# M2_USB_SATA.net
KiCad netlist of a schematic drawn in Altium Designer
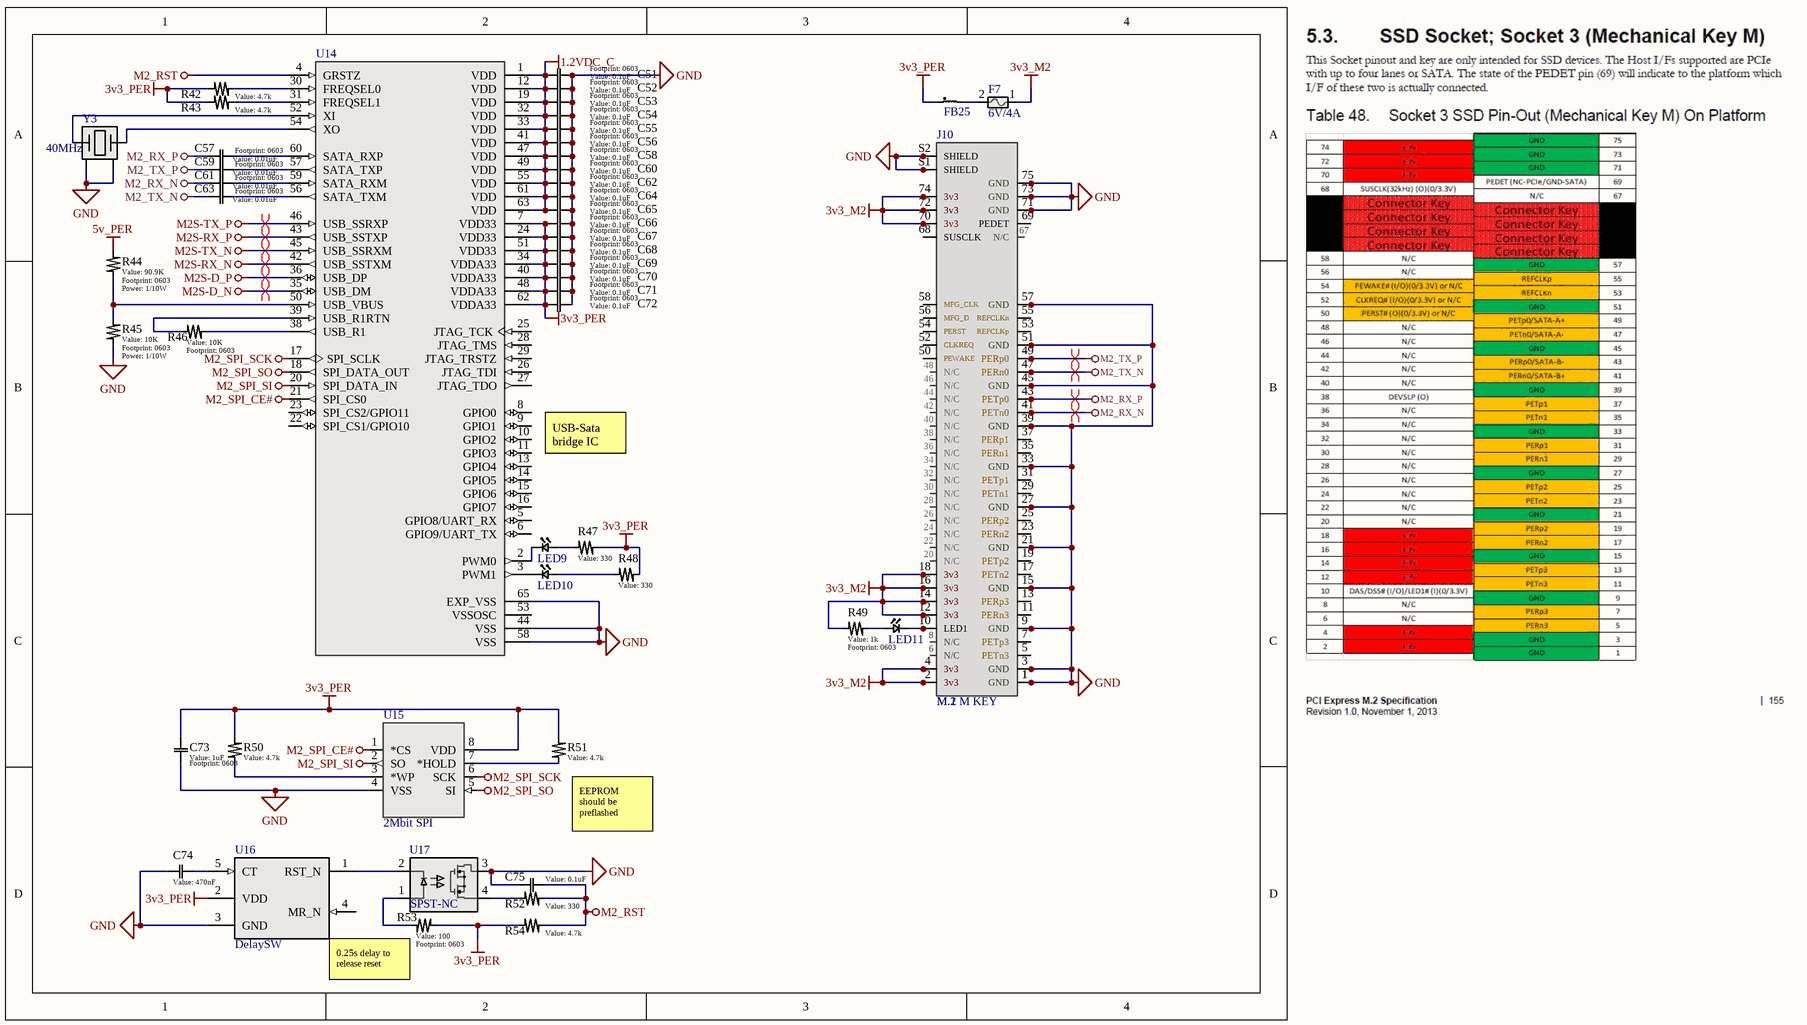
[diagram p0: M2_USB_SATA.SchDoc]

(export (version "E")
  (design (tool "Eeschema 10.0.6"))
  (components
    (comp (ref "C51")
      (value "0.1uF")
      (footprint "0603")
      (fields
        (field (name "VOLTAGE") "10V")
        (field (name "TOLERANCE") "10%")
        (field (name "Comment") "Generic Capacitor")
      )
      (libsource (lib "Capacitors") (part "Generic Capacitor"))
    )
    (comp (ref "C52")
      (value "0.1uF")
      (footprint "0603")
      (fields
        (field (name "VOLTAGE") "10V")
        (field (name "TOLERANCE") "10%")
        (field (name "Comment") "Generic Capacitor")
      )
      (libsource (lib "Capacitors") (part "Generic Capacitor"))
    )
    (comp (ref "C53")
      (value "0.1uF")
      (footprint "0603")
      (fields
        (field (name "VOLTAGE") "10V")
        (field (name "TOLERANCE") "10%")
        (field (name "Comment") "Generic Capacitor")
      )
      (libsource (lib "Capacitors") (part "Generic Capacitor"))
    )
    (comp (ref "C54")
      (value "0.1uF")
      (footprint "0603")
      (fields
        (field (name "VOLTAGE") "10V")
        (field (name "TOLERANCE") "10%")
        (field (name "Comment") "Generic Capacitor")
      )
      (libsource (lib "Capacitors") (part "Generic Capacitor"))
    )
    (comp (ref "C55")
      (value "0.1uF")
      (footprint "0603")
      (fields
        (field (name "VOLTAGE") "10V")
        (field (name "TOLERANCE") "10%")
        (field (name "Comment") "Generic Capacitor")
      )
      (libsource (lib "Capacitors") (part "Generic Capacitor"))
    )
    (comp (ref "C56")
      (value "0.1uF")
      (footprint "0603")
      (fields
        (field (name "VOLTAGE") "10V")
        (field (name "TOLERANCE") "10%")
        (field (name "Comment") "Generic Capacitor")
      )
      (libsource (lib "Capacitors") (part "Generic Capacitor"))
    )
    (comp (ref "C57")
      (value "0.01uF")
      (footprint "0603")
      (fields
        (field (name "VOLTAGE") "10V")
        (field (name "TOLERANCE") "10%")
        (field (name "Comment") "Generic Capacitor")
      )
      (libsource (lib "Capacitors") (part "Generic Capacitor"))
    )
    (comp (ref "C58")
      (value "0.1uF")
      (footprint "0603")
      (fields
        (field (name "VOLTAGE") "10V")
        (field (name "TOLERANCE") "10%")
        (field (name "Comment") "Generic Capacitor")
      )
      (libsource (lib "Capacitors") (part "Generic Capacitor"))
    )
    (comp (ref "C59")
      (value "0.01uF")
      (footprint "0603")
      (fields
        (field (name "VOLTAGE") "10V")
        (field (name "TOLERANCE") "10%")
        (field (name "Comment") "Generic Capacitor")
      )
      (libsource (lib "Capacitors") (part "Generic Capacitor"))
    )
    (comp (ref "C60")
      (value "0.1uF")
      (footprint "0603")
      (fields
        (field (name "VOLTAGE") "10V")
        (field (name "TOLERANCE") "10%")
        (field (name "Comment") "Generic Capacitor")
      )
      (libsource (lib "Capacitors") (part "Generic Capacitor"))
    )
    (comp (ref "C61")
      (value "0.01uF")
      (footprint "0603")
      (fields
        (field (name "VOLTAGE") "10V")
        (field (name "TOLERANCE") "10%")
        (field (name "Comment") "Generic Capacitor")
      )
      (libsource (lib "Capacitors") (part "Generic Capacitor"))
    )
    (comp (ref "C62")
      (value "0.1uF")
      (footprint "0603")
      (fields
        (field (name "VOLTAGE") "10V")
        (field (name "TOLERANCE") "10%")
        (field (name "Comment") "Generic Capacitor")
      )
      (libsource (lib "Capacitors") (part "Generic Capacitor"))
    )
    (comp (ref "C63")
      (value "0.01uF")
      (footprint "0603")
      (fields
        (field (name "VOLTAGE") "10V")
        (field (name "TOLERANCE") "10%")
        (field (name "Comment") "Generic Capacitor")
      )
      (libsource (lib "Capacitors") (part "Generic Capacitor"))
    )
    (comp (ref "C64")
      (value "0.1uF")
      (footprint "0603")
      (fields
        (field (name "VOLTAGE") "10V")
        (field (name "TOLERANCE") "10%")
        (field (name "Comment") "Generic Capacitor")
      )
      (libsource (lib "Capacitors") (part "Generic Capacitor"))
    )
    (comp (ref "C65")
      (value "0.1uF")
      (footprint "0603")
      (fields
        (field (name "VOLTAGE") "10V")
        (field (name "TOLERANCE") "10%")
        (field (name "Comment") "Generic Capacitor")
      )
      (libsource (lib "Capacitors") (part "Generic Capacitor"))
    )
    (comp (ref "C66")
      (value "0.1uF")
      (footprint "0603")
      (fields
        (field (name "VOLTAGE") "10V")
        (field (name "TOLERANCE") "10%")
        (field (name "Comment") "Generic Capacitor")
      )
      (libsource (lib "Capacitors") (part "Generic Capacitor"))
    )
    (comp (ref "C67")
      (value "0.1uF")
      (footprint "0603")
      (fields
        (field (name "VOLTAGE") "10V")
        (field (name "TOLERANCE") "10%")
        (field (name "Comment") "Generic Capacitor")
      )
      (libsource (lib "Capacitors") (part "Generic Capacitor"))
    )
    (comp (ref "C68")
      (value "0.1uF")
      (footprint "0603")
      (fields
        (field (name "VOLTAGE") "10V")
        (field (name "TOLERANCE") "10%")
        (field (name "Comment") "Generic Capacitor")
      )
      (libsource (lib "Capacitors") (part "Generic Capacitor"))
    )
    (comp (ref "C69")
      (value "0.1uF")
      (footprint "0603")
      (fields
        (field (name "VOLTAGE") "10V")
        (field (name "TOLERANCE") "10%")
        (field (name "Comment") "Generic Capacitor")
      )
      (libsource (lib "Capacitors") (part "Generic Capacitor"))
    )
    (comp (ref "C70")
      (value "0.1uF")
      (footprint "0603")
      (fields
        (field (name "VOLTAGE") "10V")
        (field (name "TOLERANCE") "10%")
        (field (name "Comment") "Generic Capacitor")
      )
      (libsource (lib "Capacitors") (part "Generic Capacitor"))
    )
    (comp (ref "C71")
      (value "0.1uF")
      (footprint "0603")
      (fields
        (field (name "VOLTAGE") "10V")
        (field (name "TOLERANCE") "10%")
        (field (name "Comment") "Generic Capacitor")
      )
      (libsource (lib "Capacitors") (part "Generic Capacitor"))
    )
    (comp (ref "C72")
      (value "0.1uF")
      (footprint "0603")
      (fields
        (field (name "VOLTAGE") "10V")
        (field (name "TOLERANCE") "10%")
        (field (name "Comment") "Generic Capacitor")
      )
      (libsource (lib "Capacitors") (part "Generic Capacitor"))
    )
    (comp (ref "C73")
      (value "1uF")
      (footprint "0603")
      (fields
        (field (name "VOLTAGE") ">10V")
        (field (name "TOLERANCE") "10%")
        (field (name "Comment") "Generic Capacitor")
      )
      (libsource (lib "Capacitors") (part "Generic Capacitor"))
    )
    (comp (ref "C74")
      (value "470nF")
      (footprint "0603")
      (fields
        (field (name "VOLTAGE") "10V")
        (field (name "TOLERANCE") "10%")
        (field (name "Comment") "Generic Capacitor")
      )
      (libsource (lib "Capacitors") (part "Generic Capacitor"))
    )
    (comp (ref "C75")
      (value "0.1uF")
      (footprint "0603")
      (fields
        (field (name "VOLTAGE") "10V")
        (field (name "TOLERANCE") "10%")
        (field (name "Comment") "Generic Capacitor")
      )
      (libsource (lib "Capacitors") (part "Generic Capacitor"))
    )
    (comp (ref "F7")
      (value "6V/4A")
      (footprint "0805")
      (description "Polymeric PTC Resettable Fuse 6V 1 A Ih Surface Mount 0805 (2012 Metric), Concave")
      (fields (field (name "MANUFACTURER") "Bel") (field (name "MANUFACTURER PART NUMBER") "0ZCK0100FF2E"))
      (libsource (lib "Regulators") (part "0ZCK0100FF2E"))
    )
    (comp (ref "FB25")
      (value "1206 Ferrite")
      (footprint "1206")
      (description "160 Ohms @ 100MHz 1 Power, Signal Line Ferrite Bead 1206 (3216 Metric) 6A 18mOhm")
      (libsource (lib "Inductors") (part "HI1206T161R-10"))
    )
    (comp (ref "J10")
      (value "M.2 M KEY")
      (footprint "1-2199230-6")
      (description "M.2 0.5PITCH 4.2H KEY M 30U AU")
      (fields (field (name "MF") "TE Connectivity") (field (name "DIGI-KEY_PART_NUMBER") "A118046TR-ND"))
      (libsource (lib "Connectors") (part "1-2199230-6"))
    )
    (comp (ref "LED9")
      (value "LTST-C191KGKT")
      (footprint "0603 (1608 Metric) Concave")
      (description "LED Uni-Color Green 574nm 2-Pin Chip LED T/R")
      (libsource (lib "Gamber - Johnson LLC") (part "LTST-C191KGKT"))
    )
    (comp (ref "LED10")
      (value "LTST-C191KGKT")
      (footprint "0603 (1608 Metric) Concave")
      (description "LED Uni-Color Green 574nm 2-Pin Chip LED T/R")
      (libsource (lib "Gamber - Johnson LLC") (part "LTST-C191KGKT"))
    )
    (comp (ref "LED11")
      (value "LTST-C191KGKT")
      (footprint "0603 (1608 Metric) Concave")
      (description "LED Uni-Color Green 574nm 2-Pin Chip LED T/R")
      (libsource (lib "Gamber - Johnson LLC") (part "LTST-C191KGKT"))
    )
    (comp (ref "M.1")
      (value "NVME Ref")
      (footprint "NVME-Ref 2242")
      (description "Overlay pads w/ 1-2199230-6\r\nUse standoff for mounting screws")
      (libsource (lib "SOC_Carrier") (part "NVME Ref"))
    )
    (comp (ref "R42")
      (value "4.7k")
      (footprint "0603")
      (fields
        (field (name "TOLERANCE") "1%")
        (field (name "POWER") "1/10W")
        (field (name "Comment") "Generic Resistor")
      )
      (libsource (lib "Resistors") (part "Generic Resistor"))
    )
    (comp (ref "R43")
      (value "4.7k")
      (footprint "0603")
      (fields
        (field (name "TOLERANCE") "1%")
        (field (name "POWER") "1/10W")
        (field (name "Comment") "Generic Resistor")
      )
      (libsource (lib "Resistors") (part "Generic Resistor"))
    )
    (comp (ref "R44")
      (value "90.9K")
      (footprint "0603")
      (fields
        (field (name "TOLERANCE") "1%")
        (field (name "POWER") "1/10W")
        (field (name "Comment") "Generic Resistor")
      )
      (libsource (lib "Resistors") (part "Generic Resistor"))
    )
    (comp (ref "R45")
      (value "10K")
      (footprint "0603")
      (fields
        (field (name "TOLERANCE") "1%")
        (field (name "POWER") "1/10W")
        (field (name "Comment") "Generic Resistor")
      )
      (libsource (lib "Resistors") (part "Generic Resistor"))
    )
    (comp (ref "R46")
      (value "10K")
      (footprint "0603")
      (fields
        (field (name "TOLERANCE") "1%")
        (field (name "POWER") "1/10W")
        (field (name "Comment") "Generic Resistor")
      )
      (libsource (lib "Resistors") (part "Generic Resistor"))
    )
    (comp (ref "R47")
      (value "330")
      (footprint "0603")
      (fields
        (field (name "TOLERANCE") "1%")
        (field (name "POWER") "1/10W")
        (field (name "Comment") "Generic Resistor")
      )
      (libsource (lib "Resistors") (part "Generic Resistor"))
    )
    (comp (ref "R48")
      (value "330")
      (footprint "0603")
      (fields
        (field (name "TOLERANCE") "1%")
        (field (name "POWER") "1/10W")
        (field (name "Comment") "Generic Resistor")
      )
      (libsource (lib "Resistors") (part "Generic Resistor"))
    )
    (comp (ref "R49")
      (value "1k")
      (footprint "0603")
      (fields
        (field (name "TOLERANCE") "1%")
        (field (name "POWER") "1/10W")
        (field (name "Comment") "Generic Resistor")
      )
      (libsource (lib "Resistors") (part "Generic Resistor"))
    )
    (comp (ref "R50")
      (value "4.7k")
      (footprint "0603")
      (fields
        (field (name "TOLERANCE") "1%")
        (field (name "POWER") "1/10W")
        (field (name "Comment") "Generic Resistor")
      )
      (libsource (lib "Resistors") (part "Generic Resistor"))
    )
    (comp (ref "R51")
      (value "4.7k")
      (footprint "0603")
      (fields
        (field (name "TOLERANCE") "1%")
        (field (name "POWER") "1/10W")
        (field (name "Comment") "Generic Resistor")
      )
      (libsource (lib "Resistors") (part "Generic Resistor"))
    )
    (comp (ref "R52")
      (value "330")
      (footprint "0603")
      (fields
        (field (name "TOLERANCE") "1%")
        (field (name "POWER") "1/10W")
        (field (name "Comment") "Generic Resistor")
      )
      (libsource (lib "Resistors") (part "Generic Resistor"))
    )
    (comp (ref "R53")
      (value "100")
      (footprint "0603")
      (fields
        (field (name "TOLERANCE") "1%")
        (field (name "POWER") "1/10W")
        (field (name "Comment") "Generic Resistor")
      )
      (libsource (lib "Resistors") (part "Generic Resistor"))
    )
    (comp (ref "R54")
      (value "4.7k")
      (footprint "0603")
      (fields
        (field (name "TOLERANCE") "1%")
        (field (name "POWER") "1/10W")
        (field (name "Comment") "Generic Resistor")
      )
      (libsource (lib "Resistors") (part "Generic Resistor"))
    )
    (comp (ref "U14")
      (value "USB-SATA Bridge")
      (footprint "64-HTQFP (7x7)")
      (description "HDD, CD, DVD Drive Interface 64-HTQFP _7x7_")
      (fields (field (name "MF") "Texas Instruments") (field (name "DIGI-KEY_PART_NUMBER") "296-28827-ND"))
      (libsource (lib "Misc ICs") (part "TUSB9261PVP"))
    )
    (comp (ref "U15")
      (value "2Mbit SPI")
      (footprint "8-SOIC (0.154\", 3.90mm Width)")
      (description "IC FLASH 2MBIT SPI 30MHZ 8SOP")
      (libsource (lib "Misc ICs") (part "LE25U20AMB-AH"))
    )
    (comp (ref "U16")
      (value "DelaySW")
      (footprint "TSOT-23-5")
      (description "Supervisor Open Drain or Open Collector 1 Channel SOT-23-5\r\n2.2V Threshold")
      (libsource (lib "Switches") (part "TPS3840DL22DBVR"))
    )
    (comp (ref "U17")
      (value "SPST-NC")
      (footprint "4-SOP")
      (description "SSR RELAY SPST-NC 400MA 0-60V")
      (libsource (lib "Switches") (part "CPC1117N"))
    )
    (comp (ref "Y3")
      (value "40MHz")
      (footprint "SMD3225-4P")
      (description "40MHz Surface Mount Crystal 10pF ±10ppm SMD3225-4P Crystal")
      (libsource (lib "Clock ICs") (part "L327S400H11L"))
    )
  )
  (nets
    (net (code "1") (name "1.2VDC_C") (class "Default")
      (node (ref "C51") (pin "2") (pinfunction "2_2") (pintype "passive"))
      (node (ref "C52") (pin "2") (pinfunction "2_2") (pintype "passive"))
      (node (ref "C53") (pin "2") (pinfunction "2_2") (pintype "passive"))
      (node (ref "C54") (pin "2") (pinfunction "2_2") (pintype "passive"))
      (node (ref "C55") (pin "2") (pinfunction "2_2") (pintype "passive"))
      (node (ref "C56") (pin "2") (pinfunction "2_2") (pintype "passive"))
      (node (ref "C58") (pin "2") (pinfunction "2_2") (pintype "passive"))
      (node (ref "C60") (pin "2") (pinfunction "2_2") (pintype "passive"))
      (node (ref "C62") (pin "2") (pinfunction "2_2") (pintype "passive"))
      (node (ref "C64") (pin "2") (pinfunction "2_2") (pintype "passive"))
      (node (ref "C65") (pin "2") (pinfunction "2_2") (pintype "passive"))
      (node (ref "U14") (pin "1") (pinfunction "VDD_1") (pintype "power_in"))
      (node (ref "U14") (pin "12") (pinfunction "VDD_12") (pintype "power_in"))
      (node (ref "U14") (pin "19") (pinfunction "VDD_19") (pintype "power_in"))
      (node (ref "U14") (pin "32") (pinfunction "VDD_32") (pintype "power_in"))
      (node (ref "U14") (pin "33") (pinfunction "VDD_33") (pintype "power_in"))
      (node (ref "U14") (pin "41") (pinfunction "VDD_41") (pintype "power_in"))
      (node (ref "U14") (pin "47") (pinfunction "VDD_47") (pintype "power_in"))
      (node (ref "U14") (pin "49") (pinfunction "VDD_49") (pintype "power_in"))
      (node (ref "U14") (pin "55") (pinfunction "VDD_55") (pintype "power_in"))
      (node (ref "U14") (pin "61") (pinfunction "VDD_61") (pintype "power_in"))
      (node (ref "U14") (pin "63") (pinfunction "VDD_63") (pintype "power_in"))
    )
    (net (code "2") (name "3v3_M2") (class "Default")
      (node (ref "F7") (pin "1") (pinfunction "1_1") (pintype "passive"))
      (node (ref "J10") (pin "12") (pinfunction "3v3_12") (pintype "passive"))
      (node (ref "J10") (pin "14") (pinfunction "3v3_14") (pintype "passive"))
      (node (ref "J10") (pin "16") (pinfunction "3v3_16") (pintype "passive"))
      (node (ref "J10") (pin "18") (pinfunction "3v3_18") (pintype "passive"))
      (node (ref "J10") (pin "2") (pinfunction "3v3_2") (pintype "passive"))
      (node (ref "J10") (pin "4") (pinfunction "3v3_4") (pintype "passive"))
      (node (ref "J10") (pin "70") (pinfunction "3v3_70") (pintype "passive"))
      (node (ref "J10") (pin "72") (pinfunction "3v3_72") (pintype "passive"))
      (node (ref "J10") (pin "74") (pinfunction "3v3_74") (pintype "passive"))
      (node (ref "M.1") (pin "12") (pinfunction "3v3_12") (pintype "passive"))
      (node (ref "M.1") (pin "14") (pinfunction "3v3_14") (pintype "passive"))
      (node (ref "M.1") (pin "16") (pinfunction "3v3_16") (pintype "passive"))
      (node (ref "M.1") (pin "18") (pinfunction "3v3_18") (pintype "passive"))
      (node (ref "M.1") (pin "2") (pinfunction "3v3_2") (pintype "passive"))
      (node (ref "M.1") (pin "4") (pinfunction "3v3_4") (pintype "passive"))
      (node (ref "M.1") (pin "70") (pinfunction "3v3_70") (pintype "passive"))
      (node (ref "M.1") (pin "72") (pinfunction "3v3_72") (pintype "passive"))
      (node (ref "M.1") (pin "74") (pinfunction "3v3_74") (pintype "passive"))
      (node (ref "R49") (pin "2") (pinfunction "2_2") (pintype "passive"))
    )
    (net (code "3") (name "3v3_PER") (class "Default")
      (node (ref "C66") (pin "2") (pinfunction "2_2") (pintype "passive"))
      (node (ref "C67") (pin "2") (pinfunction "2_2") (pintype "passive"))
      (node (ref "C68") (pin "2") (pinfunction "2_2") (pintype "passive"))
      (node (ref "C69") (pin "2") (pinfunction "2_2") (pintype "passive"))
      (node (ref "C70") (pin "2") (pinfunction "2_2") (pintype "passive"))
      (node (ref "C71") (pin "2") (pinfunction "2_2") (pintype "passive"))
      (node (ref "C72") (pin "2") (pinfunction "2_2") (pintype "passive"))
      (node (ref "C73") (pin "1") (pinfunction "1_1") (pintype "passive"))
      (node (ref "FB25") (pin "1") (pinfunction "1_1") (pintype "passive"))
      (node (ref "R42") (pin "1") (pinfunction "1_1") (pintype "passive"))
      (node (ref "R43") (pin "1") (pinfunction "1_1") (pintype "passive"))
      (node (ref "R47") (pin "2") (pinfunction "2_2") (pintype "passive"))
      (node (ref "R48") (pin "2") (pinfunction "2_2") (pintype "passive"))
      (node (ref "R50") (pin "1") (pinfunction "1_1") (pintype "passive"))
      (node (ref "R51") (pin "1") (pinfunction "1_1") (pintype "passive"))
      (node (ref "R53") (pin "2") (pinfunction "2_2") (pintype "passive"))
      (node (ref "R54") (pin "1") (pinfunction "1_1") (pintype "passive"))
      (node (ref "U14") (pin "24") (pinfunction "VDD33_24") (pintype "power_in"))
      (node (ref "U14") (pin "34") (pinfunction "VDDA33_34") (pintype "power_in"))
      (node (ref "U14") (pin "40") (pinfunction "VDDA33_40") (pintype "power_in"))
      (node (ref "U14") (pin "48") (pinfunction "VDDA33_48") (pintype "power_in"))
      (node (ref "U14") (pin "51") (pinfunction "VDD33_51") (pintype "power_in"))
      (node (ref "U14") (pin "62") (pinfunction "VDDA33_62") (pintype "power_in"))
      (node (ref "U14") (pin "7") (pinfunction "VDD33_7") (pintype "power_in"))
      (node (ref "U15") (pin "8") (pinfunction "VDD_8") (pintype "power_in"))
      (node (ref "U16") (pin "2") (pinfunction "VDD_2") (pintype "power_in"))
    )
    (net (code "4") (name "5v_PER") (class "Default")
      (node (ref "R44") (pin "1") (pinfunction "1_1") (pintype "passive"))
    )
    (net (code "5") (name "GND") (class "Default")
      (node (ref "C51") (pin "1") (pinfunction "1_1") (pintype "passive"))
      (node (ref "C52") (pin "1") (pinfunction "1_1") (pintype "passive"))
      (node (ref "C53") (pin "1") (pinfunction "1_1") (pintype "passive"))
      (node (ref "C54") (pin "1") (pinfunction "1_1") (pintype "passive"))
      (node (ref "C55") (pin "1") (pinfunction "1_1") (pintype "passive"))
      (node (ref "C56") (pin "1") (pinfunction "1_1") (pintype "passive"))
      (node (ref "C58") (pin "1") (pinfunction "1_1") (pintype "passive"))
      (node (ref "C60") (pin "1") (pinfunction "1_1") (pintype "passive"))
      (node (ref "C62") (pin "1") (pinfunction "1_1") (pintype "passive"))
      (node (ref "C64") (pin "1") (pinfunction "1_1") (pintype "passive"))
      (node (ref "C65") (pin "1") (pinfunction "1_1") (pintype "passive"))
      (node (ref "C66") (pin "1") (pinfunction "1_1") (pintype "passive"))
      (node (ref "C67") (pin "1") (pinfunction "1_1") (pintype "passive"))
      (node (ref "C68") (pin "1") (pinfunction "1_1") (pintype "passive"))
      (node (ref "C69") (pin "1") (pinfunction "1_1") (pintype "passive"))
      (node (ref "C70") (pin "1") (pinfunction "1_1") (pintype "passive"))
      (node (ref "C71") (pin "1") (pinfunction "1_1") (pintype "passive"))
      (node (ref "C72") (pin "1") (pinfunction "1_1") (pintype "passive"))
      (node (ref "C73") (pin "2") (pinfunction "2_2") (pintype "passive"))
      (node (ref "C74") (pin "2") (pinfunction "2_2") (pintype "passive"))
      (node (ref "C75") (pin "1") (pinfunction "1_1") (pintype "passive"))
      (node (ref "J10") (pin "1") (pinfunction "GND_1") (pintype "passive"))
      (node (ref "J10") (pin "15") (pinfunction "GND_15") (pintype "passive"))
      (node (ref "J10") (pin "21") (pinfunction "GND_21") (pintype "passive"))
      (node (ref "J10") (pin "27") (pinfunction "GND_27") (pintype "passive"))
      (node (ref "J10") (pin "3") (pinfunction "GND_3") (pintype "passive"))
      (node (ref "J10") (pin "33") (pinfunction "GND_33") (pintype "passive"))
      (node (ref "J10") (pin "39") (pinfunction "GND_39") (pintype "passive"))
      (node (ref "J10") (pin "45") (pinfunction "GND_45") (pintype "passive"))
      (node (ref "J10") (pin "51") (pinfunction "GND_51") (pintype "passive"))
      (node (ref "J10") (pin "57") (pinfunction "GND_57") (pintype "passive"))
      (node (ref "J10") (pin "71") (pinfunction "GND_71") (pintype "passive"))
      (node (ref "J10") (pin "73") (pinfunction "GND_73") (pintype "passive"))
      (node (ref "J10") (pin "75") (pinfunction "GND_75") (pintype "passive"))
      (node (ref "J10") (pin "9") (pinfunction "GND_9") (pintype "passive"))
      (node (ref "J10") (pin "S1") (pinfunction "SHIELD_S1") (pintype "passive"))
      (node (ref "J10") (pin "S2") (pinfunction "SHIELD_S2") (pintype "passive"))
      (node (ref "M.1") (pin "1") (pinfunction "GND_1") (pintype "passive"))
      (node (ref "M.1") (pin "15") (pinfunction "GND_15") (pintype "passive"))
      (node (ref "M.1") (pin "21") (pinfunction "GND_21") (pintype "passive"))
      (node (ref "M.1") (pin "27") (pinfunction "GND_27") (pintype "passive"))
      (node (ref "M.1") (pin "3") (pinfunction "GND_3") (pintype "passive"))
      (node (ref "M.1") (pin "33") (pinfunction "GND_33") (pintype "passive"))
      (node (ref "M.1") (pin "39") (pinfunction "GND_39") (pintype "passive"))
      (node (ref "M.1") (pin "45") (pinfunction "GND_45") (pintype "passive"))
      (node (ref "M.1") (pin "51") (pinfunction "GND_51") (pintype "passive"))
      (node (ref "M.1") (pin "57") (pinfunction "GND_57") (pintype "passive"))
      (node (ref "M.1") (pin "71") (pinfunction "GND_71") (pintype "passive"))
      (node (ref "M.1") (pin "73") (pinfunction "GND_73") (pintype "passive"))
      (node (ref "M.1") (pin "75") (pinfunction "GND_75") (pintype "passive"))
      (node (ref "M.1") (pin "9") (pinfunction "GND_9") (pintype "passive"))
      (node (ref "M.1") (pin "S1") (pinfunction "SHIELD_S1") (pintype "passive"))
      (node (ref "M.1") (pin "S2") (pinfunction "SHIELD_S2") (pintype "passive"))
      (node (ref "M.1") (pin "SHD") (pinfunction "SHIELD_SHD") (pintype "passive"))
      (node (ref "R45") (pin "1") (pinfunction "1_1") (pintype "passive"))
      (node (ref "U14") (pin "44") (pinfunction "VSS_44") (pintype "power_in"))
      (node (ref "U14") (pin "58") (pinfunction "VSS_58") (pintype "power_in"))
      (node (ref "U14") (pin "65") (pinfunction "EXP_VSS_65") (pintype "power_in"))
      (node (ref "U15") (pin "4") (pinfunction "VSS_4") (pintype "power_in"))
      (node (ref "U16") (pin "3") (pinfunction "GND_3") (pintype "power_in"))
      (node (ref "U17") (pin "3") (pinfunction "3_3") (pintype "passive"))
      (node (ref "Y3") (pin "2") (pinfunction "GND_2") (pintype "power_in"))
      (node (ref "Y3") (pin "4") (pinfunction "GND_4") (pintype "power_in"))
    )
    (net (code "6") (name "M2S-D_N") (class "Default")
      (node (ref "U14") (pin "35") (pinfunction "USB_DM_35") (pintype "bidirectional"))
    )
    (net (code "7") (name "M2S-D_P") (class "Default")
      (node (ref "U14") (pin "36") (pinfunction "USB_DP_36") (pintype "bidirectional"))
    )
    (net (code "8") (name "M2S-RX_N") (class "Default")
      (node (ref "U14") (pin "42") (pinfunction "USB_SSTXM_42") (pintype "output"))
    )
    (net (code "9") (name "M2S-RX_P") (class "Default")
      (node (ref "U14") (pin "43") (pinfunction "USB_SSTXP_43") (pintype "output"))
    )
    (net (code "10") (name "M2S-TX_N") (class "Default")
      (node (ref "U14") (pin "45") (pinfunction "USB_SSRXM_45") (pintype "input"))
    )
    (net (code "11") (name "M2S-TX_P") (class "Default")
      (node (ref "U14") (pin "46") (pinfunction "USB_SSRXP_46") (pintype "input"))
    )
    (net (code "12") (name "M2_RST") (class "Default")
      (node (ref "C75") (pin "2") (pinfunction "2_2") (pintype "passive"))
      (node (ref "R52") (pin "2") (pinfunction "2_2") (pintype "passive"))
      (node (ref "R54") (pin "2") (pinfunction "2_2") (pintype "passive"))
      (node (ref "U14") (pin "4") (pinfunction "GRSTZ_4") (pintype "input"))
    )
    (net (code "13") (name "M2_RX_N") (class "Default")
      (node (ref "C61") (pin "2") (pinfunction "2_2") (pintype "passive"))
      (node (ref "J10") (pin "41") (pinfunction "PETn0_41") (pintype "passive"))
      (node (ref "M.1") (pin "41") (pinfunction "PETn0_41") (pintype "passive"))
    )
    (net (code "14") (name "M2_RX_P") (class "Default")
      (node (ref "C57") (pin "2") (pinfunction "2_2") (pintype "passive"))
      (node (ref "J10") (pin "43") (pinfunction "PETp0_43") (pintype "passive"))
      (node (ref "M.1") (pin "43") (pinfunction "PETp0_43") (pintype "passive"))
    )
    (net (code "15") (name "M2_SPI_CE#") (class "Default")
      (node (ref "U14") (pin "21") (pinfunction "SPI_CS0_21") (pintype "output"))
      (node (ref "U15") (pin "1") (pinfunction "*CS_1") (pintype "passive"))
    )
    (net (code "16") (name "M2_SPI_SCK") (class "Default")
      (node (ref "U14") (pin "17") (pinfunction "SPI_SCLK_17") (pintype "output"))
      (node (ref "U15") (pin "6") (pinfunction "SCK_6") (pintype "bidirectional"))
    )
    (net (code "17") (name "M2_SPI_SI") (class "Default")
      (node (ref "U14") (pin "20") (pinfunction "SPI_DATA_IN_20") (pintype "input"))
      (node (ref "U15") (pin "2") (pinfunction "SO_2") (pintype "output"))
    )
    (net (code "18") (name "M2_SPI_SO") (class "Default")
      (node (ref "U14") (pin "18") (pinfunction "SPI_DATA_OUT_18") (pintype "output"))
      (node (ref "U15") (pin "5") (pinfunction "SI_5") (pintype "input"))
    )
    (net (code "19") (name "M2_TX_N") (class "Default")
      (node (ref "C63") (pin "2") (pinfunction "2_2") (pintype "passive"))
      (node (ref "J10") (pin "47") (pinfunction "PERn0_47") (pintype "passive"))
      (node (ref "M.1") (pin "47") (pinfunction "PERn0_47") (pintype "passive"))
    )
    (net (code "20") (name "M2_TX_P") (class "Default")
      (node (ref "C59") (pin "2") (pinfunction "2_2") (pintype "passive"))
      (node (ref "J10") (pin "49") (pinfunction "PERp0_49") (pintype "passive"))
      (node (ref "M.1") (pin "49") (pinfunction "PERp0_49") (pintype "passive"))
    )
    (net (code "21") (name "Net-(F7-Pad2)") (class "Default")
      (node (ref "F7") (pin "2") (pinfunction "2_2") (pintype "passive"))
      (node (ref "FB25") (pin "2") (pinfunction "2_2") (pintype "passive"))
    )
    (net (code "22") (name "Net-(J10-CLKREQ)") (class "Default")
      (node (ref "J10") (pin "52") (pinfunction "CLKREQ_52") (pintype "passive"))
      (node (ref "M.1") (pin "52") (pinfunction "CLKREQ_52") (pintype "passive"))
    )
    (net (code "23") (name "Net-(J10-LED1)") (class "Default")
      (node (ref "J10") (pin "10") (pinfunction "LED1_10") (pintype "passive"))
      (node (ref "LED11") (pin "1") (pinfunction "Cathode_1") (pintype "passive"))
      (node (ref "M.1") (pin "10") (pinfunction "LED1_10") (pintype "passive"))
    )
    (net (code "24") (name "Net-(J10-MFG_CLK)") (class "Default")
      (node (ref "J10") (pin "58") (pinfunction "MFG_CLK_58") (pintype "passive"))
      (node (ref "M.1") (pin "58") (pinfunction "MFG_CLK_58") (pintype "passive"))
    )
    (net (code "25") (name "Net-(J10-MFG_D)") (class "Default")
      (node (ref "J10") (pin "56") (pinfunction "MFG_D_56") (pintype "passive"))
      (node (ref "M.1") (pin "56") (pinfunction "MFG_D_56") (pintype "passive"))
    )
    (net (code "26") (name "Net-(J10-N{slash}C-Pad6)") (class "Default")
      (node (ref "J10") (pin "6") (pinfunction "N/C_6") (pintype "passive"))
      (node (ref "M.1") (pin "6") (pinfunction "N/C_6") (pintype "passive"))
    )
    (net (code "27") (name "Net-(J10-N{slash}C-Pad8)") (class "Default")
      (node (ref "J10") (pin "8") (pinfunction "N/C_8") (pintype "passive"))
      (node (ref "M.1") (pin "8") (pinfunction "N/C_8") (pintype "passive"))
    )
    (net (code "28") (name "Net-(J10-N{slash}C-Pad20)") (class "Default")
      (node (ref "J10") (pin "20") (pinfunction "N/C_20") (pintype "passive"))
      (node (ref "M.1") (pin "20") (pinfunction "N/C_20") (pintype "passive"))
    )
    (net (code "29") (name "Net-(J10-N{slash}C-Pad22)") (class "Default")
      (node (ref "J10") (pin "22") (pinfunction "N/C_22") (pintype "passive"))
      (node (ref "M.1") (pin "22") (pinfunction "N/C_22") (pintype "passive"))
    )
    (net (code "30") (name "Net-(J10-N{slash}C-Pad24)") (class "Default")
      (node (ref "J10") (pin "24") (pinfunction "N/C_24") (pintype "passive"))
      (node (ref "M.1") (pin "24") (pinfunction "N/C_24") (pintype "passive"))
    )
    (net (code "31") (name "Net-(J10-N{slash}C-Pad26)") (class "Default")
      (node (ref "J10") (pin "26") (pinfunction "N/C_26") (pintype "passive"))
      (node (ref "M.1") (pin "26") (pinfunction "N/C_26") (pintype "passive"))
    )
    (net (code "32") (name "Net-(J10-N{slash}C-Pad28)") (class "Default")
      (node (ref "J10") (pin "28") (pinfunction "N/C_28") (pintype "passive"))
      (node (ref "M.1") (pin "28") (pinfunction "N/C_28") (pintype "passive"))
    )
    (net (code "33") (name "Net-(J10-N{slash}C-Pad30)") (class "Default")
      (node (ref "J10") (pin "30") (pinfunction "N/C_30") (pintype "passive"))
      (node (ref "M.1") (pin "30") (pinfunction "N/C_30") (pintype "passive"))
    )
    (net (code "34") (name "Net-(J10-N{slash}C-Pad32)") (class "Default")
      (node (ref "J10") (pin "32") (pinfunction "N/C_32") (pintype "passive"))
      (node (ref "M.1") (pin "32") (pinfunction "N/C_32") (pintype "passive"))
    )
    (net (code "35") (name "Net-(J10-N{slash}C-Pad34)") (class "Default")
      (node (ref "J10") (pin "34") (pinfunction "N/C_34") (pintype "passive"))
      (node (ref "M.1") (pin "34") (pinfunction "N/C_34") (pintype "passive"))
    )
    (net (code "36") (name "Net-(J10-N{slash}C-Pad36)") (class "Default")
      (node (ref "J10") (pin "36") (pinfunction "N/C_36") (pintype "passive"))
      (node (ref "M.1") (pin "36") (pinfunction "N/C_36") (pintype "passive"))
    )
    (net (code "37") (name "Net-(J10-N{slash}C-Pad38)") (class "Default")
      (node (ref "J10") (pin "38") (pinfunction "N/C_38") (pintype "passive"))
      (node (ref "M.1") (pin "38") (pinfunction "N/C_38") (pintype "passive"))
    )
    (net (code "38") (name "Net-(J10-N{slash}C-Pad40)") (class "Default")
      (node (ref "J10") (pin "40") (pinfunction "N/C_40") (pintype "passive"))
      (node (ref "M.1") (pin "40") (pinfunction "N/C_40") (pintype "passive"))
    )
    (net (code "39") (name "Net-(J10-N{slash}C-Pad42)") (class "Default")
      (node (ref "J10") (pin "42") (pinfunction "N/C_42") (pintype "passive"))
      (node (ref "M.1") (pin "42") (pinfunction "N/C_42") (pintype "passive"))
    )
    (net (code "40") (name "Net-(J10-N{slash}C-Pad44)") (class "Default")
      (node (ref "J10") (pin "44") (pinfunction "N/C_44") (pintype "passive"))
      (node (ref "M.1") (pin "44") (pinfunction "N/C_44") (pintype "passive"))
    )
    (net (code "41") (name "Net-(J10-N{slash}C-Pad46)") (class "Default")
      (node (ref "J10") (pin "46") (pinfunction "N/C_46") (pintype "passive"))
      (node (ref "M.1") (pin "46") (pinfunction "N/C_46") (pintype "passive"))
    )
    (net (code "42") (name "Net-(J10-N{slash}C-Pad48)") (class "Default")
      (node (ref "J10") (pin "48") (pinfunction "N/C_48") (pintype "passive"))
      (node (ref "M.1") (pin "48") (pinfunction "N/C_48") (pintype "passive"))
    )
    (net (code "43") (name "Net-(J10-N{slash}C-Pad67)") (class "Default")
      (node (ref "J10") (pin "67") (pinfunction "N/C_67") (pintype "passive"))
      (node (ref "M.1") (pin "67") (pinfunction "N/C_67") (pintype "passive"))
    )
    (net (code "44") (name "Net-(J10-PEDET)") (class "Default")
      (node (ref "J10") (pin "69") (pinfunction "PEDET_69") (pintype "passive"))
      (node (ref "M.1") (pin "69") (pinfunction "PEDET_69") (pintype "passive"))
    )
    (net (code "45") (name "Net-(J10-PERST)") (class "Default")
      (node (ref "J10") (pin "54") (pinfunction "PERST_54") (pintype "passive"))
      (node (ref "M.1") (pin "54") (pinfunction "PERST_54") (pintype "passive"))
    )
    (net (code "46") (name "Net-(J10-PERn1)") (class "Default")
      (node (ref "J10") (pin "35") (pinfunction "PERn1_35") (pintype "passive"))
      (node (ref "M.1") (pin "35") (pinfunction "PERn1_35") (pintype "passive"))
    )
    (net (code "47") (name "Net-(J10-PERn2)") (class "Default")
      (node (ref "J10") (pin "23") (pinfunction "PERn2_23") (pintype "passive"))
      (node (ref "M.1") (pin "23") (pinfunction "PERn2_23") (pintype "passive"))
    )
    (net (code "48") (name "Net-(J10-PERn3)") (class "Default")
      (node (ref "J10") (pin "11") (pinfunction "PERn3_11") (pintype "passive"))
      (node (ref "M.1") (pin "11") (pinfunction "PERn3_11") (pintype "passive"))
    )
    (net (code "49") (name "Net-(J10-PERp1)") (class "Default")
      (node (ref "J10") (pin "37") (pinfunction "PERp1_37") (pintype "passive"))
      (node (ref "M.1") (pin "37") (pinfunction "PERp1_37") (pintype "passive"))
    )
    (net (code "50") (name "Net-(J10-PERp2)") (class "Default")
      (node (ref "J10") (pin "25") (pinfunction "PERp2_25") (pintype "passive"))
      (node (ref "M.1") (pin "25") (pinfunction "PERp2_25") (pintype "passive"))
    )
    (net (code "51") (name "Net-(J10-PERp3)") (class "Default")
      (node (ref "J10") (pin "13") (pinfunction "PERp3_13") (pintype "passive"))
      (node (ref "M.1") (pin "13") (pinfunction "PERp3_13") (pintype "passive"))
    )
    (net (code "52") (name "Net-(J10-PETn1)") (class "Default")
      (node (ref "J10") (pin "29") (pinfunction "PETn1_29") (pintype "passive"))
      (node (ref "M.1") (pin "29") (pinfunction "PETn1_29") (pintype "passive"))
    )
    (net (code "53") (name "Net-(J10-PETn2)") (class "Default")
      (node (ref "J10") (pin "17") (pinfunction "PETn2_17") (pintype "passive"))
      (node (ref "M.1") (pin "17") (pinfunction "PETn2_17") (pintype "passive"))
    )
    (net (code "54") (name "Net-(J10-PETn3)") (class "Default")
      (node (ref "J10") (pin "5") (pinfunction "PETn3_5") (pintype "passive"))
      (node (ref "M.1") (pin "5") (pinfunction "PETn3_5") (pintype "passive"))
    )
    (net (code "55") (name "Net-(J10-PETp1)") (class "Default")
      (node (ref "J10") (pin "31") (pinfunction "PETp1_31") (pintype "passive"))
      (node (ref "M.1") (pin "31") (pinfunction "PETp1_31") (pintype "passive"))
    )
    (net (code "56") (name "Net-(J10-PETp2)") (class "Default")
      (node (ref "J10") (pin "19") (pinfunction "PETp2_19") (pintype "passive"))
      (node (ref "M.1") (pin "19") (pinfunction "PETp2_19") (pintype "passive"))
    )
    (net (code "57") (name "Net-(J10-PETp3)") (class "Default")
      (node (ref "J10") (pin "7") (pinfunction "PETp3_7") (pintype "passive"))
      (node (ref "M.1") (pin "7") (pinfunction "PETp3_7") (pintype "passive"))
    )
    (net (code "58") (name "Net-(J10-PEWAKE)") (class "Default")
      (node (ref "J10") (pin "50") (pinfunction "PEWAKE_50") (pintype "passive"))
      (node (ref "M.1") (pin "50") (pinfunction "PEWAKE_50") (pintype "passive"))
    )
    (net (code "59") (name "Net-(J10-REFCLKn)") (class "Default")
      (node (ref "J10") (pin "55") (pinfunction "REFCLKn_55") (pintype "passive"))
      (node (ref "M.1") (pin "55") (pinfunction "REFCLKn_55") (pintype "passive"))
    )
    (net (code "60") (name "Net-(J10-REFCLKp)") (class "Default")
      (node (ref "J10") (pin "53") (pinfunction "REFCLKp_53") (pintype "passive"))
      (node (ref "M.1") (pin "53") (pinfunction "REFCLKp_53") (pintype "passive"))
    )
    (net (code "61") (name "Net-(J10-SUSCLK)") (class "Default")
      (node (ref "J10") (pin "68") (pinfunction "SUSCLK_68") (pintype "passive"))
      (node (ref "M.1") (pin "68") (pinfunction "SUSCLK_68") (pintype "passive"))
    )
    (net (code "62") (name "Net-(LED9-Anode)") (class "Default")
      (node (ref "LED9") (pin "2") (pinfunction "Anode_2") (pintype "passive"))
      (node (ref "R47") (pin "1") (pinfunction "1_1") (pintype "passive"))
    )
    (net (code "63") (name "Net-(LED9-Cathode)") (class "Default")
      (node (ref "LED9") (pin "1") (pinfunction "Cathode_1") (pintype "passive"))
      (node (ref "U14") (pin "2") (pinfunction "PWM0_2") (pintype "output"))
    )
    (net (code "64") (name "Net-(LED10-Anode)") (class "Default")
      (node (ref "LED10") (pin "2") (pinfunction "Anode_2") (pintype "passive"))
      (node (ref "R48") (pin "1") (pinfunction "1_1") (pintype "passive"))
    )
    (net (code "65") (name "Net-(LED10-Cathode)") (class "Default")
      (node (ref "LED10") (pin "1") (pinfunction "Cathode_1") (pintype "passive"))
      (node (ref "U14") (pin "3") (pinfunction "PWM1_3") (pintype "output"))
    )
    (net (code "66") (name "Net-(LED11-Anode)") (class "Default")
      (node (ref "LED11") (pin "2") (pinfunction "Anode_2") (pintype "passive"))
      (node (ref "R49") (pin "1") (pinfunction "1_1") (pintype "passive"))
    )
    (net (code "67") (name "Net-(R52-Pad1)") (class "Default")
      (node (ref "R52") (pin "1") (pinfunction "1_1") (pintype "passive"))
      (node (ref "U17") (pin "4") (pinfunction "4_4") (pintype "passive"))
    )
    (net (code "68") (name "Net-(R53-Pad1)") (class "Default")
      (node (ref "R53") (pin "1") (pinfunction "1_1") (pintype "passive"))
      (node (ref "U17") (pin "1") (pinfunction "1_1") (pintype "passive"))
    )
    (net (code "69") (name "Net-(U14-FREQSEL0)") (class "Default")
      (node (ref "R42") (pin "2") (pinfunction "2_2") (pintype "passive"))
      (node (ref "U14") (pin "30") (pinfunction "FREQSEL0_30") (pintype "input"))
    )
    (net (code "70") (name "Net-(U14-FREQSEL1)") (class "Default")
      (node (ref "R43") (pin "2") (pinfunction "2_2") (pintype "passive"))
      (node (ref "U14") (pin "31") (pinfunction "FREQSEL1_31") (pintype "input"))
    )
    (net (code "71") (name "Net-(U14-SATA_RXM)") (class "Default")
      (node (ref "C61") (pin "1") (pinfunction "1_1") (pintype "passive"))
      (node (ref "U14") (pin "59") (pinfunction "SATA_RXM_59") (pintype "input"))
    )
    (net (code "72") (name "Net-(U14-SATA_RXP)") (class "Default")
      (node (ref "C57") (pin "1") (pinfunction "1_1") (pintype "passive"))
      (node (ref "U14") (pin "60") (pinfunction "SATA_RXP_60") (pintype "input"))
    )
    (net (code "73") (name "Net-(U14-SATA_TXM)") (class "Default")
      (node (ref "C63") (pin "1") (pinfunction "1_1") (pintype "passive"))
      (node (ref "U14") (pin "56") (pinfunction "SATA_TXM_56") (pintype "output"))
    )
    (net (code "74") (name "Net-(U14-SATA_TXP)") (class "Default")
      (node (ref "C59") (pin "1") (pinfunction "1_1") (pintype "passive"))
      (node (ref "U14") (pin "57") (pinfunction "SATA_TXP_57") (pintype "output"))
    )
    (net (code "75") (name "Net-(U14-USB_R1)") (class "Default")
      (node (ref "R46") (pin "2") (pinfunction "2_2") (pintype "passive"))
      (node (ref "U14") (pin "38") (pinfunction "USB_R1_38") (pintype "output"))
    )
    (net (code "76") (name "Net-(U14-USB_R1RTN)") (class "Default")
      (node (ref "R46") (pin "1") (pinfunction "1_1") (pintype "passive"))
      (node (ref "U14") (pin "39") (pinfunction "USB_R1RTN_39") (pintype "input"))
    )
    (net (code "77") (name "Net-(U14-USB_VBUS)") (class "Default")
      (node (ref "R44") (pin "2") (pinfunction "2_2") (pintype "passive"))
      (node (ref "R45") (pin "2") (pinfunction "2_2") (pintype "passive"))
      (node (ref "U14") (pin "50") (pinfunction "USB_VBUS_50") (pintype "input"))
    )
    (net (code "78") (name "Net-(U14-XI)") (class "Default")
      (node (ref "U14") (pin "52") (pinfunction "XI_52") (pintype "input"))
      (node (ref "Y3") (pin "3") (pintype "passive"))
    )
    (net (code "79") (name "Net-(U14-XO)") (class "Default")
      (node (ref "U14") (pin "54") (pinfunction "XO_54") (pintype "output"))
      (node (ref "Y3") (pin "1") (pintype "passive"))
    )
    (net (code "80") (name "Net-(U15-*HOLD)") (class "Default")
      (node (ref "R51") (pin "2") (pinfunction "2_2") (pintype "passive"))
      (node (ref "U15") (pin "7") (pinfunction "*HOLD_7") (pintype "passive"))
    )
    (net (code "81") (name "Net-(U15-*WP)") (class "Default")
      (node (ref "R50") (pin "2") (pinfunction "2_2") (pintype "passive"))
      (node (ref "U15") (pin "3") (pinfunction "*WP_3") (pintype "passive"))
    )
    (net (code "82") (name "Net-(U16-CT)") (class "Default")
      (node (ref "C74") (pin "1") (pinfunction "1_1") (pintype "passive"))
      (node (ref "U16") (pin "5") (pinfunction "CT_5") (pintype "input"))
    )
    (net (code "83") (name "Net-(U16-RST_N)") (class "Default")
      (node (ref "U16") (pin "1") (pinfunction "RST_N_1") (pintype "open_collector"))
      (node (ref "U17") (pin "2") (pinfunction "2_2") (pintype "passive"))
    )
    (net (code "84") (name "unconnected-(U14-GPIO0-Pad8)") (class "Default")
      (node (ref "U14") (pin "8") (pinfunction "GPIO0_8") (pintype "bidirectional"))
    )
    (net (code "85") (name "unconnected-(U14-GPIO1-Pad9)") (class "Default")
      (node (ref "U14") (pin "9") (pinfunction "GPIO1_9") (pintype "bidirectional"))
    )
    (net (code "86") (name "unconnected-(U14-GPIO2-Pad10)") (class "Default")
      (node (ref "U14") (pin "10") (pinfunction "GPIO2_10") (pintype "bidirectional"))
    )
    (net (code "87") (name "unconnected-(U14-GPIO3-Pad11)") (class "Default")
      (node (ref "U14") (pin "11") (pinfunction "GPIO3_11") (pintype "bidirectional"))
    )
    (net (code "88") (name "unconnected-(U14-GPIO4-Pad13)") (class "Default")
      (node (ref "U14") (pin "13") (pinfunction "GPIO4_13") (pintype "bidirectional"))
    )
    (net (code "89") (name "unconnected-(U14-GPIO5-Pad14)") (class "Default")
      (node (ref "U14") (pin "14") (pinfunction "GPIO5_14") (pintype "bidirectional"))
    )
    (net (code "90") (name "unconnected-(U14-GPIO6-Pad15)") (class "Default")
      (node (ref "U14") (pin "15") (pinfunction "GPIO6_15") (pintype "bidirectional"))
    )
    (net (code "91") (name "unconnected-(U14-GPIO7-Pad16)") (class "Default")
      (node (ref "U14") (pin "16") (pinfunction "GPIO7_16") (pintype "bidirectional"))
    )
    (net (code "92") (name "unconnected-(U14-GPIO8{slash}UART_RX-Pad5)") (class "Default")
      (node (ref "U14") (pin "5") (pinfunction "GPIO8/UART_RX_5") (pintype "bidirectional"))
    )
    (net (code "93") (name "unconnected-(U14-GPIO9{slash}UART_TX-Pad6)") (class "Default")
      (node (ref "U14") (pin "6") (pinfunction "GPIO9/UART_TX_6") (pintype "bidirectional"))
    )
    (net (code "94") (name "unconnected-(U14-JTAG_TCK-Pad25)") (class "Default")
      (node (ref "U14") (pin "25") (pinfunction "JTAG_TCK_25") (pintype "input"))
    )
    (net (code "95") (name "unconnected-(U14-JTAG_TDI-Pad26)") (class "Default")
      (node (ref "U14") (pin "26") (pinfunction "JTAG_TDI_26") (pintype "input"))
    )
    (net (code "96") (name "unconnected-(U14-JTAG_TDO-Pad27)") (class "Default")
      (node (ref "U14") (pin "27") (pinfunction "JTAG_TDO_27") (pintype "output"))
    )
    (net (code "97") (name "unconnected-(U14-JTAG_TMS-Pad28)") (class "Default")
      (node (ref "U14") (pin "28") (pinfunction "JTAG_TMS_28") (pintype "input"))
    )
    (net (code "98") (name "unconnected-(U14-JTAG_TRSTZ-Pad29)") (class "Default")
      (node (ref "U14") (pin "29") (pinfunction "JTAG_TRSTZ_29") (pintype "input"))
    )
    (net (code "99") (name "unconnected-(U14-SPI_CS1{slash}GPIO10-Pad22)") (class "Default")
      (node (ref "U14") (pin "22") (pinfunction "SPI_CS1/GPIO10_22") (pintype "bidirectional"))
    )
    (net (code "100") (name "unconnected-(U14-SPI_CS2{slash}GPIO11-Pad23)") (class "Default")
      (node (ref "U14") (pin "23") (pinfunction "SPI_CS2/GPIO11_23") (pintype "bidirectional"))
    )
    (net (code "101") (name "unconnected-(U14-VSSOSC-Pad53)") (class "Default")
      (node (ref "U14") (pin "53") (pinfunction "VSSOSC_53") (pintype "power_in"))
    )
    (net (code "102") (name "unconnected-(U16-MR_N-Pad4)") (class "Default")
      (node (ref "U16") (pin "4") (pinfunction "MR_N_4") (pintype "input"))
    )
  )
)
